# 4_Button_Array_LED_V2.net
KiCad netlist of a schematic drawn in EAGLE
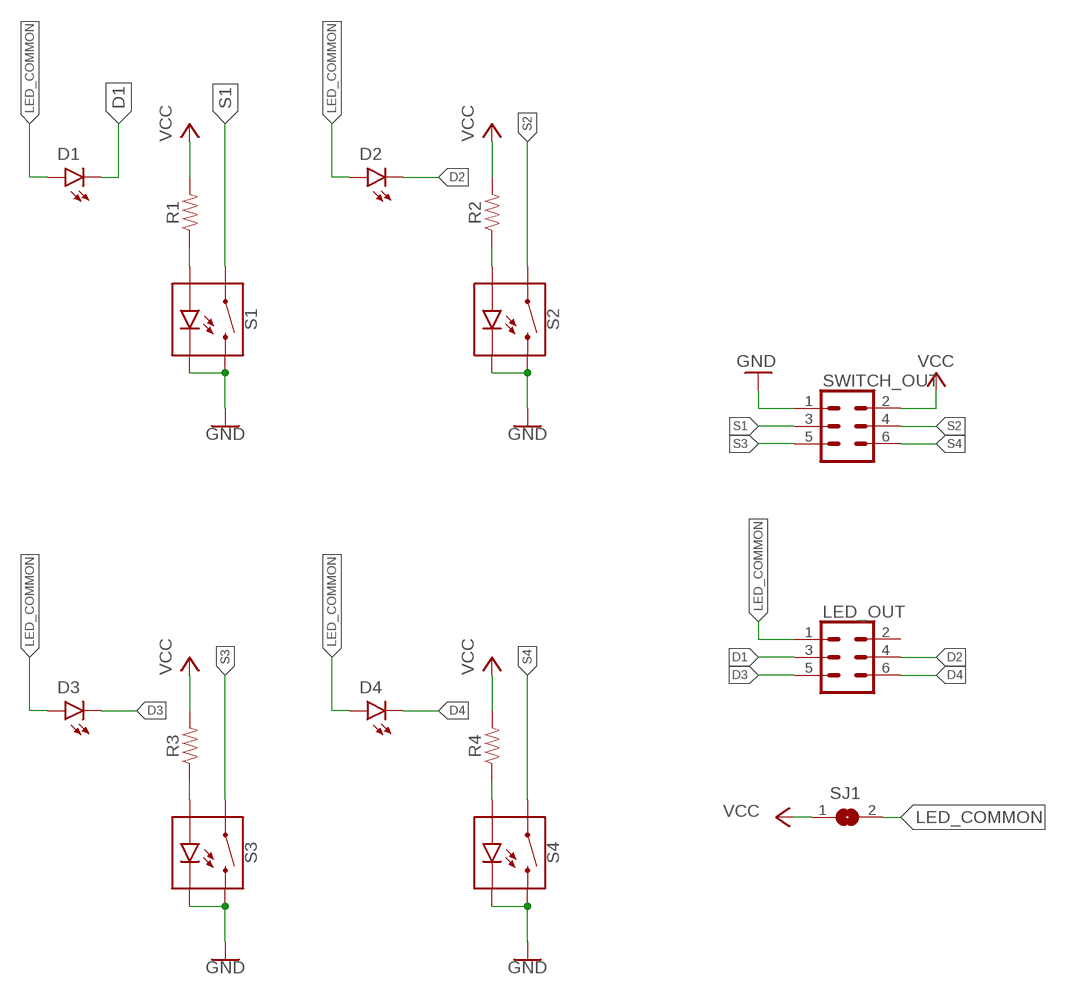
[diagram p0: schematic, sheet 1]

(export (version "E")
  (design (tool "Eeschema 10.0.6"))
  (components
    (comp (ref "D1")
      (value "LED3MM")
      (footprint "eagle-import:LED_3MM")
      (libsource (lib "eagle-import") (part "LED3MM"))
    )
    (comp (ref "D2")
      (value "LED3MM")
      (footprint "eagle-import:LED_3MM")
      (libsource (lib "eagle-import") (part "LED3MM"))
    )
    (comp (ref "D3")
      (value "LED3MM")
      (footprint "eagle-import:LED_3MM")
      (libsource (lib "eagle-import") (part "LED3MM"))
    )
    (comp (ref "D4")
      (value "LED3MM")
      (footprint "eagle-import:LED_3MM")
      (libsource (lib "eagle-import") (part "LED3MM"))
    )
    (comp (ref "LED_OUT")
      (value "CONN_03X2SHROUD")
      (footprint "eagle-import:2X3-SHROUDED")
      (libsource (lib "eagle-import") (part "CONN_03X2SHROUD"))
    )
    (comp (ref "R1")
      (value "RESISTOR1206")
      (footprint "eagle-import:1206")
      (libsource (lib "eagle-import") (part "RESISTOR1206"))
    )
    (comp (ref "R2")
      (value "RESISTOR1206")
      (footprint "eagle-import:1206")
      (libsource (lib "eagle-import") (part "RESISTOR1206"))
    )
    (comp (ref "R3")
      (value "RESISTOR1206")
      (footprint "eagle-import:1206")
      (libsource (lib "eagle-import") (part "RESISTOR1206"))
    )
    (comp (ref "R4")
      (value "RESISTOR1206")
      (footprint "eagle-import:1206")
      (libsource (lib "eagle-import") (part "RESISTOR1206"))
    )
    (comp (ref "S1")
      (value "MOMENTARY-SWITCH-SPST-LED-PTH-12MM")
      (footprint "eagle-import:TACTILE_SWITCH_LED_PTH_12MM")
      (libsource (lib "eagle-import") (part "MOMENTARY-SWITCH-SPST-LED-PTH-12MM"))
    )
    (comp (ref "S2")
      (value "MOMENTARY-SWITCH-SPST-LED-PTH-12MM")
      (footprint "eagle-import:TACTILE_SWITCH_LED_PTH_12MM")
      (libsource (lib "eagle-import") (part "MOMENTARY-SWITCH-SPST-LED-PTH-12MM"))
    )
    (comp (ref "S3")
      (value "MOMENTARY-SWITCH-SPST-LED-PTH-12MM")
      (footprint "eagle-import:TACTILE_SWITCH_LED_PTH_12MM")
      (libsource (lib "eagle-import") (part "MOMENTARY-SWITCH-SPST-LED-PTH-12MM"))
    )
    (comp (ref "S4")
      (value "MOMENTARY-SWITCH-SPST-LED-PTH-12MM")
      (footprint "eagle-import:TACTILE_SWITCH_LED_PTH_12MM")
      (libsource (lib "eagle-import") (part "MOMENTARY-SWITCH-SPST-LED-PTH-12MM"))
    )
    (comp (ref "SJ1") (value "SJ") (footprint "eagle-import:SJ") (libsource (lib "eagle-import") (part "SJ")))
    (comp (ref "SWITCH_OUT")
      (value "CONN_03X2SHROUD")
      (footprint "eagle-import:2X3-SHROUDED")
      (libsource (lib "eagle-import") (part "CONN_03X2SHROUD"))
    )
  )
  (nets
    (net (code "1") (name "D1") (class "Default")
      (node (ref "D1") (pin "K") (pinfunction "C_K") (pintype "passive"))
      (node (ref "LED_OUT") (pin "3") (pinfunction "3_3") (pintype "bidirectional"))
    )
    (net (code "2") (name "D2") (class "Default")
      (node (ref "D2") (pin "K") (pinfunction "C_K") (pintype "passive"))
      (node (ref "LED_OUT") (pin "4") (pinfunction "4_4") (pintype "bidirectional"))
    )
    (net (code "3") (name "D3") (class "Default")
      (node (ref "D3") (pin "K") (pinfunction "C_K") (pintype "passive"))
      (node (ref "LED_OUT") (pin "5") (pinfunction "5_5") (pintype "bidirectional"))
    )
    (net (code "4") (name "D4") (class "Default")
      (node (ref "D4") (pin "K") (pinfunction "C_K") (pintype "passive"))
      (node (ref "LED_OUT") (pin "6") (pinfunction "6_6") (pintype "bidirectional"))
    )
    (net (code "5") (name "GND") (class "Default")
      (node (ref "S1") (pin "2") (pinfunction "2_2") (pintype "passive"))
      (node (ref "S1") (pin "C") (pinfunction "C_C") (pintype "passive"))
      (node (ref "S2") (pin "2") (pinfunction "2_2") (pintype "passive"))
      (node (ref "S2") (pin "C") (pinfunction "C_C") (pintype "passive"))
      (node (ref "S3") (pin "2") (pinfunction "2_2") (pintype "passive"))
      (node (ref "S3") (pin "C") (pinfunction "C_C") (pintype "passive"))
      (node (ref "S4") (pin "2") (pinfunction "2_2") (pintype "passive"))
      (node (ref "S4") (pin "C") (pinfunction "C_C") (pintype "passive"))
      (node (ref "SWITCH_OUT") (pin "1") (pinfunction "1_1") (pintype "bidirectional"))
    )
    (net (code "6") (name "LED_COMMON") (class "Default")
      (node (ref "D1") (pin "A") (pinfunction "A_A") (pintype "passive"))
      (node (ref "D2") (pin "A") (pinfunction "A_A") (pintype "passive"))
      (node (ref "D3") (pin "A") (pinfunction "A_A") (pintype "passive"))
      (node (ref "D4") (pin "A") (pinfunction "A_A") (pintype "passive"))
      (node (ref "LED_OUT") (pin "1") (pinfunction "1_1") (pintype "bidirectional"))
      (node (ref "SJ1") (pin "2") (pinfunction "2_2") (pintype "passive"))
    )
    (net (code "7") (name "Net-(R1-Pad1)") (class "Default")
      (node (ref "R1") (pin "1") (pinfunction "1_1") (pintype "passive"))
      (node (ref "S1") (pin "A") (pinfunction "A_A") (pintype "passive"))
    )
    (net (code "8") (name "Net-(R2-Pad1)") (class "Default")
      (node (ref "R2") (pin "1") (pinfunction "1_1") (pintype "passive"))
      (node (ref "S2") (pin "A") (pinfunction "A_A") (pintype "passive"))
    )
    (net (code "9") (name "Net-(R3-Pad1)") (class "Default")
      (node (ref "R3") (pin "1") (pinfunction "1_1") (pintype "passive"))
      (node (ref "S3") (pin "A") (pinfunction "A_A") (pintype "passive"))
    )
    (net (code "10") (name "Net-(R4-Pad1)") (class "Default")
      (node (ref "R4") (pin "1") (pinfunction "1_1") (pintype "passive"))
      (node (ref "S4") (pin "A") (pinfunction "A_A") (pintype "passive"))
    )
    (net (code "11") (name "S1") (class "Default")
      (node (ref "S1") (pin "4") (pinfunction "1_4") (pintype "passive"))
      (node (ref "SWITCH_OUT") (pin "3") (pinfunction "3_3") (pintype "bidirectional"))
    )
    (net (code "12") (name "S2") (class "Default")
      (node (ref "S2") (pin "4") (pinfunction "1_4") (pintype "passive"))
      (node (ref "SWITCH_OUT") (pin "4") (pinfunction "4_4") (pintype "bidirectional"))
    )
    (net (code "13") (name "S3") (class "Default")
      (node (ref "S3") (pin "4") (pinfunction "1_4") (pintype "passive"))
      (node (ref "SWITCH_OUT") (pin "5") (pinfunction "5_5") (pintype "bidirectional"))
    )
    (net (code "14") (name "S4") (class "Default")
      (node (ref "S4") (pin "4") (pinfunction "1_4") (pintype "passive"))
      (node (ref "SWITCH_OUT") (pin "6") (pinfunction "6_6") (pintype "bidirectional"))
    )
    (net (code "15") (name "VCC") (class "Default")
      (node (ref "R1") (pin "2") (pinfunction "2_2") (pintype "passive"))
      (node (ref "R2") (pin "2") (pinfunction "2_2") (pintype "passive"))
      (node (ref "R3") (pin "2") (pinfunction "2_2") (pintype "passive"))
      (node (ref "R4") (pin "2") (pinfunction "2_2") (pintype "passive"))
      (node (ref "SJ1") (pin "1") (pinfunction "1_1") (pintype "passive"))
      (node (ref "SWITCH_OUT") (pin "2") (pinfunction "2_2") (pintype "bidirectional"))
    )
    (net (code "16") (name "unconnected-(LED_OUT-Pad2)") (class "Default")
      (node (ref "LED_OUT") (pin "2") (pinfunction "2_2") (pintype "bidirectional"))
    )
  )
)
